# 2nd_version.net
KiCad netlist of a schematic drawn in EAGLE
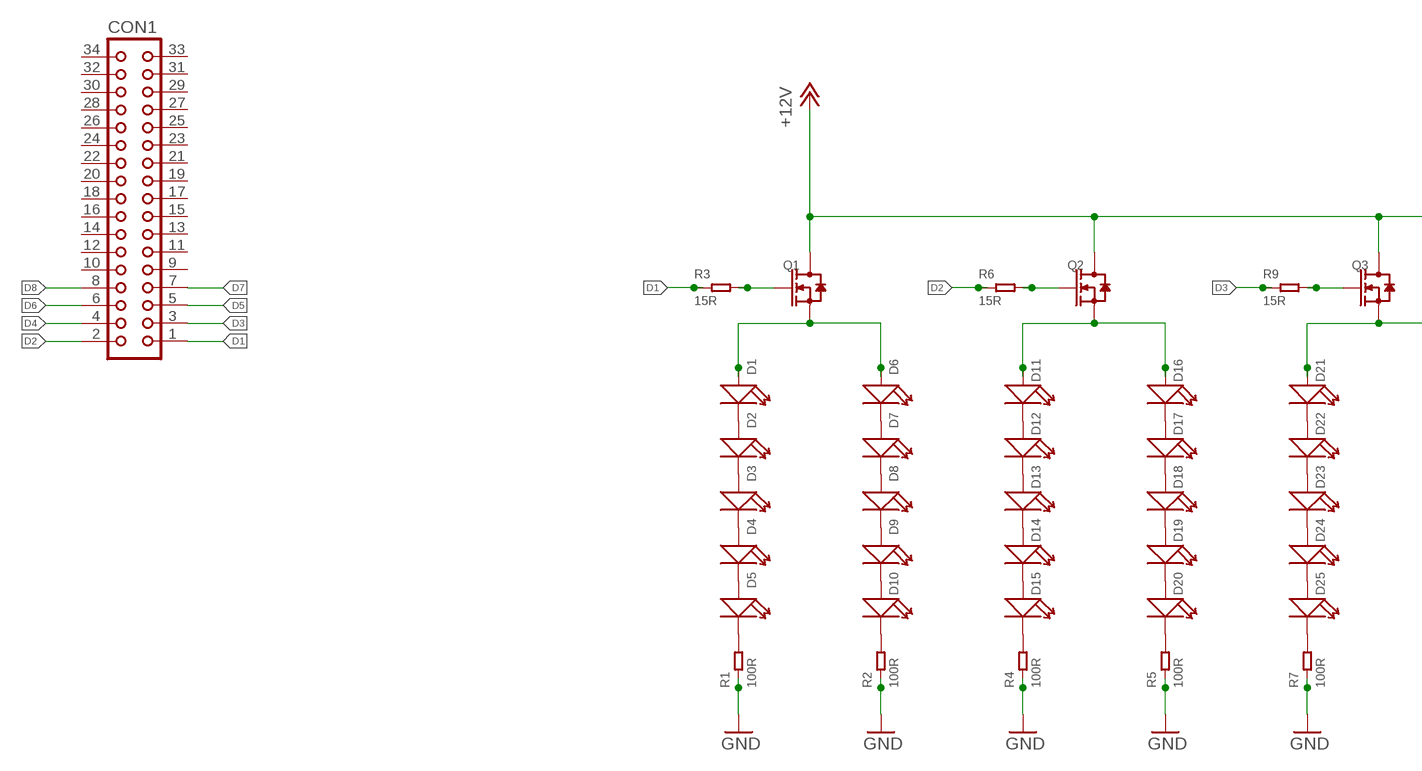
[diagram p0: schematic, sheet 1, part 1 of 2]
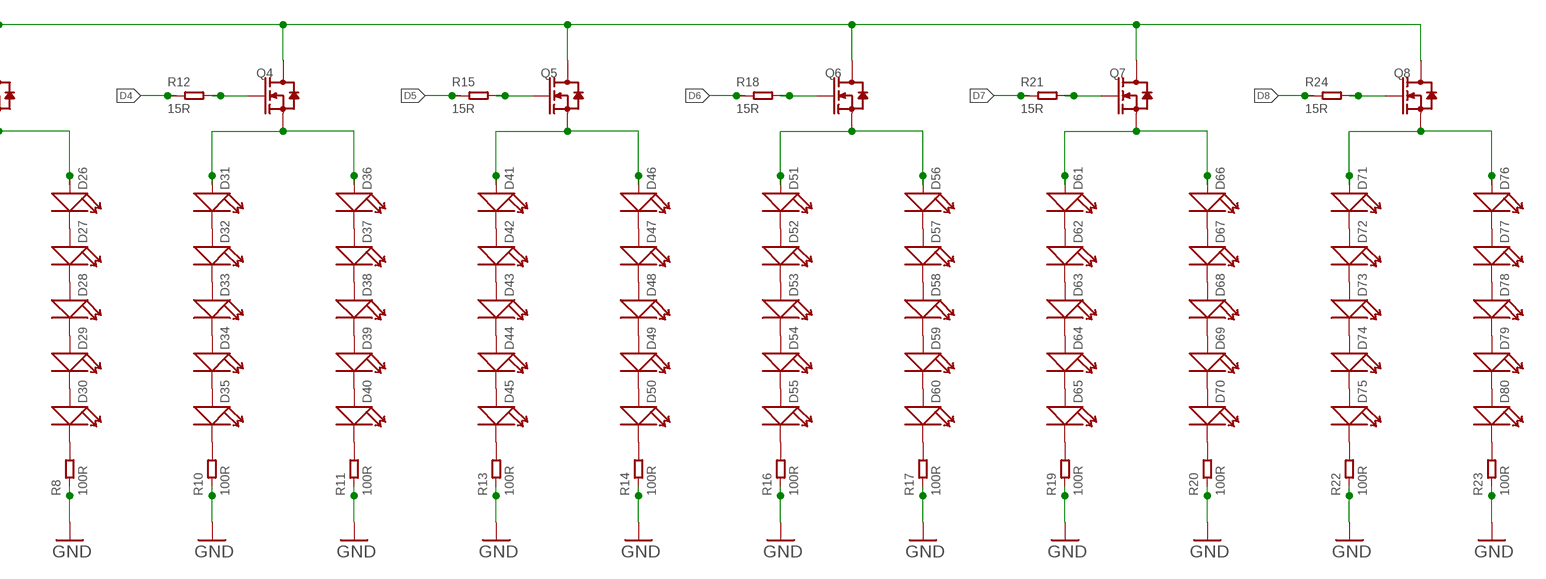
[diagram p1: schematic, sheet 1, part 2 of 2]

(export (version "E")
  (design (tool "Eeschema 10.0.6"))
  (components
    (comp (ref "CON1")
      (value "CON34L")
      (footprint "eagle-import:CON34L")
      (libsource (lib "eagle-import") (part "CON34L"))
    )
    (comp (ref "D1")
      (value "SMD-LED-CLEAR-YELLOW(0603)")
      (footprint "eagle-import:LED-0603")
      (fields (field (name "MPN") "19-217-Y5C-AM1N1VY-3T"))
      (libsource (lib "eagle-import") (part "SMD-LED-CLEAR-YELLOW(0603)"))
    )
    (comp (ref "D2")
      (value "SMD-LED-CLEAR-YELLOW(0603)")
      (footprint "eagle-import:LED-0603")
      (fields (field (name "MPN") "19-217-Y5C-AM1N1VY-3T"))
      (libsource (lib "eagle-import") (part "SMD-LED-CLEAR-YELLOW(0603)"))
    )
    (comp (ref "D3")
      (value "SMD-LED-CLEAR-YELLOW(0603)")
      (footprint "eagle-import:LED-0603")
      (fields (field (name "MPN") "19-217-Y5C-AM1N1VY-3T"))
      (libsource (lib "eagle-import") (part "SMD-LED-CLEAR-YELLOW(0603)"))
    )
    (comp (ref "D4")
      (value "SMD-LED-CLEAR-YELLOW(0603)")
      (footprint "eagle-import:LED-0603")
      (fields (field (name "MPN") "19-217-Y5C-AM1N1VY-3T"))
      (libsource (lib "eagle-import") (part "SMD-LED-CLEAR-YELLOW(0603)"))
    )
    (comp (ref "D5")
      (value "SMD-LED-CLEAR-YELLOW(0603)")
      (footprint "eagle-import:LED-0603")
      (fields (field (name "MPN") "19-217-Y5C-AM1N1VY-3T"))
      (libsource (lib "eagle-import") (part "SMD-LED-CLEAR-YELLOW(0603)"))
    )
    (comp (ref "D6")
      (value "SMD-LED-CLEAR-YELLOW(0603)")
      (footprint "eagle-import:LED-0603")
      (fields (field (name "MPN") "19-217-Y5C-AM1N1VY-3T"))
      (libsource (lib "eagle-import") (part "SMD-LED-CLEAR-YELLOW(0603)"))
    )
    (comp (ref "D7")
      (value "SMD-LED-CLEAR-YELLOW(0603)")
      (footprint "eagle-import:LED-0603")
      (fields (field (name "MPN") "19-217-Y5C-AM1N1VY-3T"))
      (libsource (lib "eagle-import") (part "SMD-LED-CLEAR-YELLOW(0603)"))
    )
    (comp (ref "D8")
      (value "SMD-LED-CLEAR-YELLOW(0603)")
      (footprint "eagle-import:LED-0603")
      (fields (field (name "MPN") "19-217-Y5C-AM1N1VY-3T"))
      (libsource (lib "eagle-import") (part "SMD-LED-CLEAR-YELLOW(0603)"))
    )
    (comp (ref "D9")
      (value "SMD-LED-CLEAR-YELLOW(0603)")
      (footprint "eagle-import:LED-0603")
      (fields (field (name "MPN") "19-217-Y5C-AM1N1VY-3T"))
      (libsource (lib "eagle-import") (part "SMD-LED-CLEAR-YELLOW(0603)"))
    )
    (comp (ref "D10")
      (value "SMD-LED-CLEAR-YELLOW(0603)")
      (footprint "eagle-import:LED-0603")
      (fields (field (name "MPN") "19-217-Y5C-AM1N1VY-3T"))
      (libsource (lib "eagle-import") (part "SMD-LED-CLEAR-YELLOW(0603)"))
    )
    (comp (ref "D11")
      (value "SMD-LED-CLEAR-YELLOW(0603)")
      (footprint "eagle-import:LED-0603")
      (fields (field (name "MPN") "19-217-Y5C-AM1N1VY-3T"))
      (libsource (lib "eagle-import") (part "SMD-LED-CLEAR-YELLOW(0603)"))
    )
    (comp (ref "D12")
      (value "SMD-LED-CLEAR-YELLOW(0603)")
      (footprint "eagle-import:LED-0603")
      (fields (field (name "MPN") "19-217-Y5C-AM1N1VY-3T"))
      (libsource (lib "eagle-import") (part "SMD-LED-CLEAR-YELLOW(0603)"))
    )
    (comp (ref "D13")
      (value "SMD-LED-CLEAR-YELLOW(0603)")
      (footprint "eagle-import:LED-0603")
      (fields (field (name "MPN") "19-217-Y5C-AM1N1VY-3T"))
      (libsource (lib "eagle-import") (part "SMD-LED-CLEAR-YELLOW(0603)"))
    )
    (comp (ref "D14")
      (value "SMD-LED-CLEAR-YELLOW(0603)")
      (footprint "eagle-import:LED-0603")
      (fields (field (name "MPN") "19-217-Y5C-AM1N1VY-3T"))
      (libsource (lib "eagle-import") (part "SMD-LED-CLEAR-YELLOW(0603)"))
    )
    (comp (ref "D15")
      (value "SMD-LED-CLEAR-YELLOW(0603)")
      (footprint "eagle-import:LED-0603")
      (fields (field (name "MPN") "19-217-Y5C-AM1N1VY-3T"))
      (libsource (lib "eagle-import") (part "SMD-LED-CLEAR-YELLOW(0603)"))
    )
    (comp (ref "D16")
      (value "SMD-LED-CLEAR-YELLOW(0603)")
      (footprint "eagle-import:LED-0603")
      (fields (field (name "MPN") "19-217-Y5C-AM1N1VY-3T"))
      (libsource (lib "eagle-import") (part "SMD-LED-CLEAR-YELLOW(0603)"))
    )
    (comp (ref "D17")
      (value "SMD-LED-CLEAR-YELLOW(0603)")
      (footprint "eagle-import:LED-0603")
      (fields (field (name "MPN") "19-217-Y5C-AM1N1VY-3T"))
      (libsource (lib "eagle-import") (part "SMD-LED-CLEAR-YELLOW(0603)"))
    )
    (comp (ref "D18")
      (value "SMD-LED-CLEAR-YELLOW(0603)")
      (footprint "eagle-import:LED-0603")
      (fields (field (name "MPN") "19-217-Y5C-AM1N1VY-3T"))
      (libsource (lib "eagle-import") (part "SMD-LED-CLEAR-YELLOW(0603)"))
    )
    (comp (ref "D19")
      (value "SMD-LED-CLEAR-YELLOW(0603)")
      (footprint "eagle-import:LED-0603")
      (fields (field (name "MPN") "19-217-Y5C-AM1N1VY-3T"))
      (libsource (lib "eagle-import") (part "SMD-LED-CLEAR-YELLOW(0603)"))
    )
    (comp (ref "D20")
      (value "SMD-LED-CLEAR-YELLOW(0603)")
      (footprint "eagle-import:LED-0603")
      (fields (field (name "MPN") "19-217-Y5C-AM1N1VY-3T"))
      (libsource (lib "eagle-import") (part "SMD-LED-CLEAR-YELLOW(0603)"))
    )
    (comp (ref "D21")
      (value "SMD-LED-CLEAR-YELLOW(0603)")
      (footprint "eagle-import:LED-0603")
      (fields (field (name "MPN") "19-217-Y5C-AM1N1VY-3T"))
      (libsource (lib "eagle-import") (part "SMD-LED-CLEAR-YELLOW(0603)"))
    )
    (comp (ref "D22")
      (value "SMD-LED-CLEAR-YELLOW(0603)")
      (footprint "eagle-import:LED-0603")
      (fields (field (name "MPN") "19-217-Y5C-AM1N1VY-3T"))
      (libsource (lib "eagle-import") (part "SMD-LED-CLEAR-YELLOW(0603)"))
    )
    (comp (ref "D23")
      (value "SMD-LED-CLEAR-YELLOW(0603)")
      (footprint "eagle-import:LED-0603")
      (fields (field (name "MPN") "19-217-Y5C-AM1N1VY-3T"))
      (libsource (lib "eagle-import") (part "SMD-LED-CLEAR-YELLOW(0603)"))
    )
    (comp (ref "D24")
      (value "SMD-LED-CLEAR-YELLOW(0603)")
      (footprint "eagle-import:LED-0603")
      (fields (field (name "MPN") "19-217-Y5C-AM1N1VY-3T"))
      (libsource (lib "eagle-import") (part "SMD-LED-CLEAR-YELLOW(0603)"))
    )
    (comp (ref "D25")
      (value "SMD-LED-CLEAR-YELLOW(0603)")
      (footprint "eagle-import:LED-0603")
      (fields (field (name "MPN") "19-217-Y5C-AM1N1VY-3T"))
      (libsource (lib "eagle-import") (part "SMD-LED-CLEAR-YELLOW(0603)"))
    )
    (comp (ref "D26")
      (value "SMD-LED-CLEAR-YELLOW(0603)")
      (footprint "eagle-import:LED-0603")
      (fields (field (name "MPN") "19-217-Y5C-AM1N1VY-3T"))
      (libsource (lib "eagle-import") (part "SMD-LED-CLEAR-YELLOW(0603)"))
    )
    (comp (ref "D27")
      (value "SMD-LED-CLEAR-YELLOW(0603)")
      (footprint "eagle-import:LED-0603")
      (fields (field (name "MPN") "19-217-Y5C-AM1N1VY-3T"))
      (libsource (lib "eagle-import") (part "SMD-LED-CLEAR-YELLOW(0603)"))
    )
    (comp (ref "D28")
      (value "SMD-LED-CLEAR-YELLOW(0603)")
      (footprint "eagle-import:LED-0603")
      (fields (field (name "MPN") "19-217-Y5C-AM1N1VY-3T"))
      (libsource (lib "eagle-import") (part "SMD-LED-CLEAR-YELLOW(0603)"))
    )
    (comp (ref "D29")
      (value "SMD-LED-CLEAR-YELLOW(0603)")
      (footprint "eagle-import:LED-0603")
      (fields (field (name "MPN") "19-217-Y5C-AM1N1VY-3T"))
      (libsource (lib "eagle-import") (part "SMD-LED-CLEAR-YELLOW(0603)"))
    )
    (comp (ref "D30")
      (value "SMD-LED-CLEAR-YELLOW(0603)")
      (footprint "eagle-import:LED-0603")
      (fields (field (name "MPN") "19-217-Y5C-AM1N1VY-3T"))
      (libsource (lib "eagle-import") (part "SMD-LED-CLEAR-YELLOW(0603)"))
    )
    (comp (ref "D31")
      (value "SMD-LED-CLEAR-YELLOW(0603)")
      (footprint "eagle-import:LED-0603")
      (fields (field (name "MPN") "19-217-Y5C-AM1N1VY-3T"))
      (libsource (lib "eagle-import") (part "SMD-LED-CLEAR-YELLOW(0603)"))
    )
    (comp (ref "D32")
      (value "SMD-LED-CLEAR-YELLOW(0603)")
      (footprint "eagle-import:LED-0603")
      (fields (field (name "MPN") "19-217-Y5C-AM1N1VY-3T"))
      (libsource (lib "eagle-import") (part "SMD-LED-CLEAR-YELLOW(0603)"))
    )
    (comp (ref "D33")
      (value "SMD-LED-CLEAR-YELLOW(0603)")
      (footprint "eagle-import:LED-0603")
      (fields (field (name "MPN") "19-217-Y5C-AM1N1VY-3T"))
      (libsource (lib "eagle-import") (part "SMD-LED-CLEAR-YELLOW(0603)"))
    )
    (comp (ref "D34")
      (value "SMD-LED-CLEAR-YELLOW(0603)")
      (footprint "eagle-import:LED-0603")
      (fields (field (name "MPN") "19-217-Y5C-AM1N1VY-3T"))
      (libsource (lib "eagle-import") (part "SMD-LED-CLEAR-YELLOW(0603)"))
    )
    (comp (ref "D35")
      (value "SMD-LED-CLEAR-YELLOW(0603)")
      (footprint "eagle-import:LED-0603")
      (fields (field (name "MPN") "19-217-Y5C-AM1N1VY-3T"))
      (libsource (lib "eagle-import") (part "SMD-LED-CLEAR-YELLOW(0603)"))
    )
    (comp (ref "D36")
      (value "SMD-LED-CLEAR-YELLOW(0603)")
      (footprint "eagle-import:LED-0603")
      (fields (field (name "MPN") "19-217-Y5C-AM1N1VY-3T"))
      (libsource (lib "eagle-import") (part "SMD-LED-CLEAR-YELLOW(0603)"))
    )
    (comp (ref "D37")
      (value "SMD-LED-CLEAR-YELLOW(0603)")
      (footprint "eagle-import:LED-0603")
      (fields (field (name "MPN") "19-217-Y5C-AM1N1VY-3T"))
      (libsource (lib "eagle-import") (part "SMD-LED-CLEAR-YELLOW(0603)"))
    )
    (comp (ref "D38")
      (value "SMD-LED-CLEAR-YELLOW(0603)")
      (footprint "eagle-import:LED-0603")
      (fields (field (name "MPN") "19-217-Y5C-AM1N1VY-3T"))
      (libsource (lib "eagle-import") (part "SMD-LED-CLEAR-YELLOW(0603)"))
    )
    (comp (ref "D39")
      (value "SMD-LED-CLEAR-YELLOW(0603)")
      (footprint "eagle-import:LED-0603")
      (fields (field (name "MPN") "19-217-Y5C-AM1N1VY-3T"))
      (libsource (lib "eagle-import") (part "SMD-LED-CLEAR-YELLOW(0603)"))
    )
    (comp (ref "D40")
      (value "SMD-LED-CLEAR-YELLOW(0603)")
      (footprint "eagle-import:LED-0603")
      (fields (field (name "MPN") "19-217-Y5C-AM1N1VY-3T"))
      (libsource (lib "eagle-import") (part "SMD-LED-CLEAR-YELLOW(0603)"))
    )
    (comp (ref "D41")
      (value "SMD-LED-CLEAR-YELLOW(0603)")
      (footprint "eagle-import:LED-0603")
      (fields (field (name "MPN") "19-217-Y5C-AM1N1VY-3T"))
      (libsource (lib "eagle-import") (part "SMD-LED-CLEAR-YELLOW(0603)"))
    )
    (comp (ref "D42")
      (value "SMD-LED-CLEAR-YELLOW(0603)")
      (footprint "eagle-import:LED-0603")
      (fields (field (name "MPN") "19-217-Y5C-AM1N1VY-3T"))
      (libsource (lib "eagle-import") (part "SMD-LED-CLEAR-YELLOW(0603)"))
    )
    (comp (ref "D43")
      (value "SMD-LED-CLEAR-YELLOW(0603)")
      (footprint "eagle-import:LED-0603")
      (fields (field (name "MPN") "19-217-Y5C-AM1N1VY-3T"))
      (libsource (lib "eagle-import") (part "SMD-LED-CLEAR-YELLOW(0603)"))
    )
    (comp (ref "D44")
      (value "SMD-LED-CLEAR-YELLOW(0603)")
      (footprint "eagle-import:LED-0603")
      (fields (field (name "MPN") "19-217-Y5C-AM1N1VY-3T"))
      (libsource (lib "eagle-import") (part "SMD-LED-CLEAR-YELLOW(0603)"))
    )
    (comp (ref "D45")
      (value "SMD-LED-CLEAR-YELLOW(0603)")
      (footprint "eagle-import:LED-0603")
      (fields (field (name "MPN") "19-217-Y5C-AM1N1VY-3T"))
      (libsource (lib "eagle-import") (part "SMD-LED-CLEAR-YELLOW(0603)"))
    )
    (comp (ref "D46")
      (value "SMD-LED-CLEAR-YELLOW(0603)")
      (footprint "eagle-import:LED-0603")
      (fields (field (name "MPN") "19-217-Y5C-AM1N1VY-3T"))
      (libsource (lib "eagle-import") (part "SMD-LED-CLEAR-YELLOW(0603)"))
    )
    (comp (ref "D47")
      (value "SMD-LED-CLEAR-YELLOW(0603)")
      (footprint "eagle-import:LED-0603")
      (fields (field (name "MPN") "19-217-Y5C-AM1N1VY-3T"))
      (libsource (lib "eagle-import") (part "SMD-LED-CLEAR-YELLOW(0603)"))
    )
    (comp (ref "D48")
      (value "SMD-LED-CLEAR-YELLOW(0603)")
      (footprint "eagle-import:LED-0603")
      (fields (field (name "MPN") "19-217-Y5C-AM1N1VY-3T"))
      (libsource (lib "eagle-import") (part "SMD-LED-CLEAR-YELLOW(0603)"))
    )
    (comp (ref "D49")
      (value "SMD-LED-CLEAR-YELLOW(0603)")
      (footprint "eagle-import:LED-0603")
      (fields (field (name "MPN") "19-217-Y5C-AM1N1VY-3T"))
      (libsource (lib "eagle-import") (part "SMD-LED-CLEAR-YELLOW(0603)"))
    )
    (comp (ref "D50")
      (value "SMD-LED-CLEAR-YELLOW(0603)")
      (footprint "eagle-import:LED-0603")
      (fields (field (name "MPN") "19-217-Y5C-AM1N1VY-3T"))
      (libsource (lib "eagle-import") (part "SMD-LED-CLEAR-YELLOW(0603)"))
    )
    (comp (ref "D51")
      (value "SMD-LED-CLEAR-YELLOW(0603)")
      (footprint "eagle-import:LED-0603")
      (fields (field (name "MPN") "19-217-Y5C-AM1N1VY-3T"))
      (libsource (lib "eagle-import") (part "SMD-LED-CLEAR-YELLOW(0603)"))
    )
    (comp (ref "D52")
      (value "SMD-LED-CLEAR-YELLOW(0603)")
      (footprint "eagle-import:LED-0603")
      (fields (field (name "MPN") "19-217-Y5C-AM1N1VY-3T"))
      (libsource (lib "eagle-import") (part "SMD-LED-CLEAR-YELLOW(0603)"))
    )
    (comp (ref "D53")
      (value "SMD-LED-CLEAR-YELLOW(0603)")
      (footprint "eagle-import:LED-0603")
      (fields (field (name "MPN") "19-217-Y5C-AM1N1VY-3T"))
      (libsource (lib "eagle-import") (part "SMD-LED-CLEAR-YELLOW(0603)"))
    )
    (comp (ref "D54")
      (value "SMD-LED-CLEAR-YELLOW(0603)")
      (footprint "eagle-import:LED-0603")
      (fields (field (name "MPN") "19-217-Y5C-AM1N1VY-3T"))
      (libsource (lib "eagle-import") (part "SMD-LED-CLEAR-YELLOW(0603)"))
    )
    (comp (ref "D55")
      (value "SMD-LED-CLEAR-YELLOW(0603)")
      (footprint "eagle-import:LED-0603")
      (fields (field (name "MPN") "19-217-Y5C-AM1N1VY-3T"))
      (libsource (lib "eagle-import") (part "SMD-LED-CLEAR-YELLOW(0603)"))
    )
    (comp (ref "D56")
      (value "SMD-LED-CLEAR-YELLOW(0603)")
      (footprint "eagle-import:LED-0603")
      (fields (field (name "MPN") "19-217-Y5C-AM1N1VY-3T"))
      (libsource (lib "eagle-import") (part "SMD-LED-CLEAR-YELLOW(0603)"))
    )
    (comp (ref "D57")
      (value "SMD-LED-CLEAR-YELLOW(0603)")
      (footprint "eagle-import:LED-0603")
      (fields (field (name "MPN") "19-217-Y5C-AM1N1VY-3T"))
      (libsource (lib "eagle-import") (part "SMD-LED-CLEAR-YELLOW(0603)"))
    )
    (comp (ref "D58")
      (value "SMD-LED-CLEAR-YELLOW(0603)")
      (footprint "eagle-import:LED-0603")
      (fields (field (name "MPN") "19-217-Y5C-AM1N1VY-3T"))
      (libsource (lib "eagle-import") (part "SMD-LED-CLEAR-YELLOW(0603)"))
    )
    (comp (ref "D59")
      (value "SMD-LED-CLEAR-YELLOW(0603)")
      (footprint "eagle-import:LED-0603")
      (fields (field (name "MPN") "19-217-Y5C-AM1N1VY-3T"))
      (libsource (lib "eagle-import") (part "SMD-LED-CLEAR-YELLOW(0603)"))
    )
    (comp (ref "D60")
      (value "SMD-LED-CLEAR-YELLOW(0603)")
      (footprint "eagle-import:LED-0603")
      (fields (field (name "MPN") "19-217-Y5C-AM1N1VY-3T"))
      (libsource (lib "eagle-import") (part "SMD-LED-CLEAR-YELLOW(0603)"))
    )
    (comp (ref "D61")
      (value "SMD-LED-CLEAR-YELLOW(0603)")
      (footprint "eagle-import:LED-0603")
      (fields (field (name "MPN") "19-217-Y5C-AM1N1VY-3T"))
      (libsource (lib "eagle-import") (part "SMD-LED-CLEAR-YELLOW(0603)"))
    )
    (comp (ref "D62")
      (value "SMD-LED-CLEAR-YELLOW(0603)")
      (footprint "eagle-import:LED-0603")
      (fields (field (name "MPN") "19-217-Y5C-AM1N1VY-3T"))
      (libsource (lib "eagle-import") (part "SMD-LED-CLEAR-YELLOW(0603)"))
    )
    (comp (ref "D63")
      (value "SMD-LED-CLEAR-YELLOW(0603)")
      (footprint "eagle-import:LED-0603")
      (fields (field (name "MPN") "19-217-Y5C-AM1N1VY-3T"))
      (libsource (lib "eagle-import") (part "SMD-LED-CLEAR-YELLOW(0603)"))
    )
    (comp (ref "D64")
      (value "SMD-LED-CLEAR-YELLOW(0603)")
      (footprint "eagle-import:LED-0603")
      (fields (field (name "MPN") "19-217-Y5C-AM1N1VY-3T"))
      (libsource (lib "eagle-import") (part "SMD-LED-CLEAR-YELLOW(0603)"))
    )
    (comp (ref "D65")
      (value "SMD-LED-CLEAR-YELLOW(0603)")
      (footprint "eagle-import:LED-0603")
      (fields (field (name "MPN") "19-217-Y5C-AM1N1VY-3T"))
      (libsource (lib "eagle-import") (part "SMD-LED-CLEAR-YELLOW(0603)"))
    )
    (comp (ref "D66")
      (value "SMD-LED-CLEAR-YELLOW(0603)")
      (footprint "eagle-import:LED-0603")
      (fields (field (name "MPN") "19-217-Y5C-AM1N1VY-3T"))
      (libsource (lib "eagle-import") (part "SMD-LED-CLEAR-YELLOW(0603)"))
    )
    (comp (ref "D67")
      (value "SMD-LED-CLEAR-YELLOW(0603)")
      (footprint "eagle-import:LED-0603")
      (fields (field (name "MPN") "19-217-Y5C-AM1N1VY-3T"))
      (libsource (lib "eagle-import") (part "SMD-LED-CLEAR-YELLOW(0603)"))
    )
    (comp (ref "D68")
      (value "SMD-LED-CLEAR-YELLOW(0603)")
      (footprint "eagle-import:LED-0603")
      (fields (field (name "MPN") "19-217-Y5C-AM1N1VY-3T"))
      (libsource (lib "eagle-import") (part "SMD-LED-CLEAR-YELLOW(0603)"))
    )
    (comp (ref "D69")
      (value "SMD-LED-CLEAR-YELLOW(0603)")
      (footprint "eagle-import:LED-0603")
      (fields (field (name "MPN") "19-217-Y5C-AM1N1VY-3T"))
      (libsource (lib "eagle-import") (part "SMD-LED-CLEAR-YELLOW(0603)"))
    )
    (comp (ref "D70")
      (value "SMD-LED-CLEAR-YELLOW(0603)")
      (footprint "eagle-import:LED-0603")
      (fields (field (name "MPN") "19-217-Y5C-AM1N1VY-3T"))
      (libsource (lib "eagle-import") (part "SMD-LED-CLEAR-YELLOW(0603)"))
    )
    (comp (ref "D71")
      (value "SMD-LED-CLEAR-YELLOW(0603)")
      (footprint "eagle-import:LED-0603")
      (fields (field (name "MPN") "19-217-Y5C-AM1N1VY-3T"))
      (libsource (lib "eagle-import") (part "SMD-LED-CLEAR-YELLOW(0603)"))
    )
    (comp (ref "D72")
      (value "SMD-LED-CLEAR-YELLOW(0603)")
      (footprint "eagle-import:LED-0603")
      (fields (field (name "MPN") "19-217-Y5C-AM1N1VY-3T"))
      (libsource (lib "eagle-import") (part "SMD-LED-CLEAR-YELLOW(0603)"))
    )
    (comp (ref "D73")
      (value "SMD-LED-CLEAR-YELLOW(0603)")
      (footprint "eagle-import:LED-0603")
      (fields (field (name "MPN") "19-217-Y5C-AM1N1VY-3T"))
      (libsource (lib "eagle-import") (part "SMD-LED-CLEAR-YELLOW(0603)"))
    )
    (comp (ref "D74")
      (value "SMD-LED-CLEAR-YELLOW(0603)")
      (footprint "eagle-import:LED-0603")
      (fields (field (name "MPN") "19-217-Y5C-AM1N1VY-3T"))
      (libsource (lib "eagle-import") (part "SMD-LED-CLEAR-YELLOW(0603)"))
    )
    (comp (ref "D75")
      (value "SMD-LED-CLEAR-YELLOW(0603)")
      (footprint "eagle-import:LED-0603")
      (fields (field (name "MPN") "19-217-Y5C-AM1N1VY-3T"))
      (libsource (lib "eagle-import") (part "SMD-LED-CLEAR-YELLOW(0603)"))
    )
    (comp (ref "D76")
      (value "SMD-LED-CLEAR-YELLOW(0603)")
      (footprint "eagle-import:LED-0603")
      (fields (field (name "MPN") "19-217-Y5C-AM1N1VY-3T"))
      (libsource (lib "eagle-import") (part "SMD-LED-CLEAR-YELLOW(0603)"))
    )
    (comp (ref "D77")
      (value "SMD-LED-CLEAR-YELLOW(0603)")
      (footprint "eagle-import:LED-0603")
      (fields (field (name "MPN") "19-217-Y5C-AM1N1VY-3T"))
      (libsource (lib "eagle-import") (part "SMD-LED-CLEAR-YELLOW(0603)"))
    )
    (comp (ref "D78")
      (value "SMD-LED-CLEAR-YELLOW(0603)")
      (footprint "eagle-import:LED-0603")
      (fields (field (name "MPN") "19-217-Y5C-AM1N1VY-3T"))
      (libsource (lib "eagle-import") (part "SMD-LED-CLEAR-YELLOW(0603)"))
    )
    (comp (ref "D79")
      (value "SMD-LED-CLEAR-YELLOW(0603)")
      (footprint "eagle-import:LED-0603")
      (fields (field (name "MPN") "19-217-Y5C-AM1N1VY-3T"))
      (libsource (lib "eagle-import") (part "SMD-LED-CLEAR-YELLOW(0603)"))
    )
    (comp (ref "D80")
      (value "SMD-LED-CLEAR-YELLOW(0603)")
      (footprint "eagle-import:LED-0603")
      (fields (field (name "MPN") "19-217-Y5C-AM1N1VY-3T"))
      (libsource (lib "eagle-import") (part "SMD-LED-CLEAR-YELLOW(0603)"))
    )
    (comp (ref "Q1")
      (value "SMD-MOSFET-N-CH-20V-2.1A(SOT-23)")
      (footprint "eagle-import:SOT-23")
      (fields (field (name "MPN") "CJ2302"))
      (libsource (lib "eagle-import") (part "SMD-MOSFET-N-CH-20V-2.1A(SOT-23)"))
    )
    (comp (ref "Q2")
      (value "SMD-MOSFET-N-CH-20V-2.1A(SOT-23)")
      (footprint "eagle-import:SOT-23")
      (fields (field (name "MPN") "CJ2302"))
      (libsource (lib "eagle-import") (part "SMD-MOSFET-N-CH-20V-2.1A(SOT-23)"))
    )
    (comp (ref "Q3")
      (value "SMD-MOSFET-N-CH-20V-2.1A(SOT-23)")
      (footprint "eagle-import:SOT-23")
      (fields (field (name "MPN") "CJ2302"))
      (libsource (lib "eagle-import") (part "SMD-MOSFET-N-CH-20V-2.1A(SOT-23)"))
    )
    (comp (ref "Q4")
      (value "SMD-MOSFET-N-CH-20V-2.1A(SOT-23)")
      (footprint "eagle-import:SOT-23")
      (fields (field (name "MPN") "CJ2302"))
      (libsource (lib "eagle-import") (part "SMD-MOSFET-N-CH-20V-2.1A(SOT-23)"))
    )
    (comp (ref "Q5")
      (value "SMD-MOSFET-N-CH-20V-2.1A(SOT-23)")
      (footprint "eagle-import:SOT-23")
      (fields (field (name "MPN") "CJ2302"))
      (libsource (lib "eagle-import") (part "SMD-MOSFET-N-CH-20V-2.1A(SOT-23)"))
    )
    (comp (ref "Q6")
      (value "SMD-MOSFET-N-CH-20V-2.1A(SOT-23)")
      (footprint "eagle-import:SOT-23")
      (fields (field (name "MPN") "CJ2302"))
      (libsource (lib "eagle-import") (part "SMD-MOSFET-N-CH-20V-2.1A(SOT-23)"))
    )
    (comp (ref "Q7")
      (value "SMD-MOSFET-N-CH-20V-2.1A(SOT-23)")
      (footprint "eagle-import:SOT-23")
      (fields (field (name "MPN") "CJ2302"))
      (libsource (lib "eagle-import") (part "SMD-MOSFET-N-CH-20V-2.1A(SOT-23)"))
    )
    (comp (ref "Q8")
      (value "SMD-MOSFET-N-CH-20V-2.1A(SOT-23)")
      (footprint "eagle-import:SOT-23")
      (fields (field (name "MPN") "CJ2302"))
      (libsource (lib "eagle-import") (part "SMD-MOSFET-N-CH-20V-2.1A(SOT-23)"))
    )
    (comp (ref "R1")
      (value "100R")
      (footprint "eagle-import:R0805")
      (fields (field (name "MPN") "RC0805JR-07100RL"))
      (libsource (lib "eagle-import") (part "SMD-RES-100R-5%-1/8W(0805)"))
    )
    (comp (ref "R2")
      (value "100R")
      (footprint "eagle-import:R0805")
      (fields (field (name "MPN") "RC0805JR-07100RL"))
      (libsource (lib "eagle-import") (part "SMD-RES-100R-5%-1/8W(0805)"))
    )
    (comp (ref "R3")
      (value "15R")
      (footprint "eagle-import:R0603")
      (fields (field (name "MPN") "RC0603JR-0715RL"))
      (libsource (lib "eagle-import") (part "SMD-RES-15R-5%-1/10W(0603)"))
    )
    (comp (ref "R4")
      (value "100R")
      (footprint "eagle-import:R0805")
      (fields (field (name "MPN") "RC0805JR-07100RL"))
      (libsource (lib "eagle-import") (part "SMD-RES-100R-5%-1/8W(0805)"))
    )
    (comp (ref "R5")
      (value "100R")
      (footprint "eagle-import:R0805")
      (fields (field (name "MPN") "RC0805JR-07100RL"))
      (libsource (lib "eagle-import") (part "SMD-RES-100R-5%-1/8W(0805)"))
    )
    (comp (ref "R6")
      (value "15R")
      (footprint "eagle-import:R0603")
      (fields (field (name "MPN") "RC0603JR-0715RL"))
      (libsource (lib "eagle-import") (part "SMD-RES-15R-5%-1/10W(0603)"))
    )
    (comp (ref "R7")
      (value "100R")
      (footprint "eagle-import:R0805")
      (fields (field (name "MPN") "RC0805JR-07100RL"))
      (libsource (lib "eagle-import") (part "SMD-RES-100R-5%-1/8W(0805)"))
    )
    (comp (ref "R8")
      (value "100R")
      (footprint "eagle-import:R0805")
      (fields (field (name "MPN") "RC0805JR-07100RL"))
      (libsource (lib "eagle-import") (part "SMD-RES-100R-5%-1/8W(0805)"))
    )
    (comp (ref "R9")
      (value "15R")
      (footprint "eagle-import:R0603")
      (fields (field (name "MPN") "RC0603JR-0715RL"))
      (libsource (lib "eagle-import") (part "SMD-RES-15R-5%-1/10W(0603)"))
    )
    (comp (ref "R10")
      (value "100R")
      (footprint "eagle-import:R0805")
      (fields (field (name "MPN") "RC0805JR-07100RL"))
      (libsource (lib "eagle-import") (part "SMD-RES-100R-5%-1/8W(0805)"))
    )
    (comp (ref "R11")
      (value "100R")
      (footprint "eagle-import:R0805")
      (fields (field (name "MPN") "RC0805JR-07100RL"))
      (libsource (lib "eagle-import") (part "SMD-RES-100R-5%-1/8W(0805)"))
    )
    (comp (ref "R12")
      (value "15R")
      (footprint "eagle-import:R0603")
      (fields (field (name "MPN") "RC0603JR-0715RL"))
      (libsource (lib "eagle-import") (part "SMD-RES-15R-5%-1/10W(0603)"))
    )
    (comp (ref "R13")
      (value "100R")
      (footprint "eagle-import:R0805")
      (fields (field (name "MPN") "RC0805JR-07100RL"))
      (libsource (lib "eagle-import") (part "SMD-RES-100R-5%-1/8W(0805)"))
    )
    (comp (ref "R14")
      (value "100R")
      (footprint "eagle-import:R0805")
      (fields (field (name "MPN") "RC0805JR-07100RL"))
      (libsource (lib "eagle-import") (part "SMD-RES-100R-5%-1/8W(0805)"))
    )
    (comp (ref "R15")
      (value "15R")
      (footprint "eagle-import:R0603")
      (fields (field (name "MPN") "RC0603JR-0715RL"))
      (libsource (lib "eagle-import") (part "SMD-RES-15R-5%-1/10W(0603)"))
    )
    (comp (ref "R16")
      (value "100R")
      (footprint "eagle-import:R0805")
      (fields (field (name "MPN") "RC0805JR-07100RL"))
      (libsource (lib "eagle-import") (part "SMD-RES-100R-5%-1/8W(0805)"))
    )
    (comp (ref "R17")
      (value "100R")
      (footprint "eagle-import:R0805")
      (fields (field (name "MPN") "RC0805JR-07100RL"))
      (libsource (lib "eagle-import") (part "SMD-RES-100R-5%-1/8W(0805)"))
    )
    (comp (ref "R18")
      (value "15R")
      (footprint "eagle-import:R0603")
      (fields (field (name "MPN") "RC0603JR-0715RL"))
      (libsource (lib "eagle-import") (part "SMD-RES-15R-5%-1/10W(0603)"))
    )
    (comp (ref "R19")
      (value "100R")
      (footprint "eagle-import:R0805")
      (fields (field (name "MPN") "RC0805JR-07100RL"))
      (libsource (lib "eagle-import") (part "SMD-RES-100R-5%-1/8W(0805)"))
    )
    (comp (ref "R20")
      (value "100R")
      (footprint "eagle-import:R0805")
      (fields (field (name "MPN") "RC0805JR-07100RL"))
      (libsource (lib "eagle-import") (part "SMD-RES-100R-5%-1/8W(0805)"))
    )
    (comp (ref "R21")
      (value "15R")
      (footprint "eagle-import:R0603")
      (fields (field (name "MPN") "RC0603JR-0715RL"))
      (libsource (lib "eagle-import") (part "SMD-RES-15R-5%-1/10W(0603)"))
    )
    (comp (ref "R22")
      (value "100R")
      (footprint "eagle-import:R0805")
      (fields (field (name "MPN") "RC0805JR-07100RL"))
      (libsource (lib "eagle-import") (part "SMD-RES-100R-5%-1/8W(0805)"))
    )
    (comp (ref "R23")
      (value "100R")
      (footprint "eagle-import:R0805")
      (fields (field (name "MPN") "RC0805JR-07100RL"))
      (libsource (lib "eagle-import") (part "SMD-RES-100R-5%-1/8W(0805)"))
    )
    (comp (ref "R24")
      (value "15R")
      (footprint "eagle-import:R0603")
      (fields (field (name "MPN") "RC0603JR-0715RL"))
      (libsource (lib "eagle-import") (part "SMD-RES-15R-5%-1/10W(0603)"))
    )
  )
  (nets
    (net (code "1") (name "+12V") (class "Default")
      (node (ref "Q1") (pin "3") (pinfunction "D_3") (pintype "passive"))
      (node (ref "Q2") (pin "3") (pinfunction "D_3") (pintype "passive"))
      (node (ref "Q3") (pin "3") (pinfunction "D_3") (pintype "passive"))
      (node (ref "Q4") (pin "3") (pinfunction "D_3") (pintype "passive"))
      (node (ref "Q5") (pin "3") (pinfunction "D_3") (pintype "passive"))
      (node (ref "Q6") (pin "3") (pinfunction "D_3") (pintype "passive"))
      (node (ref "Q7") (pin "3") (pinfunction "D_3") (pintype "passive"))
      (node (ref "Q8") (pin "3") (pinfunction "D_3") (pintype "passive"))
    )
    (net (code "2") (name "D1") (class "Default")
      (node (ref "CON1") (pin "1") (pinfunction "1_1") (pintype "passive"))
      (node (ref "R3") (pin "1") (pinfunction "1_1") (pintype "passive"))
    )
    (net (code "3") (name "D2") (class "Default")
      (node (ref "CON1") (pin "2") (pinfunction "2_2") (pintype "passive"))
      (node (ref "R6") (pin "1") (pinfunction "1_1") (pintype "passive"))
    )
    (net (code "4") (name "D3") (class "Default")
      (node (ref "CON1") (pin "3") (pinfunction "3_3") (pintype "passive"))
      (node (ref "R9") (pin "1") (pinfunction "1_1") (pintype "passive"))
    )
    (net (code "5") (name "D4") (class "Default")
      (node (ref "CON1") (pin "4") (pinfunction "4_4") (pintype "passive"))
      (node (ref "R12") (pin "1") (pinfunction "1_1") (pintype "passive"))
    )
    (net (code "6") (name "D5") (class "Default")
      (node (ref "CON1") (pin "5") (pinfunction "5_5") (pintype "passive"))
      (node (ref "R15") (pin "1") (pinfunction "1_1") (pintype "passive"))
    )
    (net (code "7") (name "D6") (class "Default")
      (node (ref "CON1") (pin "6") (pinfunction "6_6") (pintype "passive"))
      (node (ref "R18") (pin "1") (pinfunction "1_1") (pintype "passive"))
    )
    (net (code "8") (name "D7") (class "Default")
      (node (ref "CON1") (pin "7") (pinfunction "7_7") (pintype "passive"))
      (node (ref "R21") (pin "1") (pinfunction "1_1") (pintype "passive"))
    )
    (net (code "9") (name "D8") (class "Default")
      (node (ref "CON1") (pin "8") (pinfunction "8_8") (pintype "passive"))
      (node (ref "R24") (pin "1") (pinfunction "1_1") (pintype "passive"))
    )
    (net (code "10") (name "GND") (class "Default")
      (node (ref "R1") (pin "1") (pinfunction "1_1") (pintype "passive"))
      (node (ref "R10") (pin "1") (pinfunction "1_1") (pintype "passive"))
      (node (ref "R11") (pin "1") (pinfunction "1_1") (pintype "passive"))
      (node (ref "R13") (pin "1") (pinfunction "1_1") (pintype "passive"))
      (node (ref "R14") (pin "1") (pinfunction "1_1") (pintype "passive"))
      (node (ref "R16") (pin "1") (pinfunction "1_1") (pintype "passive"))
      (node (ref "R17") (pin "1") (pinfunction "1_1") (pintype "passive"))
      (node (ref "R19") (pin "1") (pinfunction "1_1") (pintype "passive"))
      (node (ref "R2") (pin "1") (pinfunction "1_1") (pintype "passive"))
      (node (ref "R20") (pin "1") (pinfunction "1_1") (pintype "passive"))
      (node (ref "R22") (pin "1") (pinfunction "1_1") (pintype "passive"))
      (node (ref "R23") (pin "1") (pinfunction "1_1") (pintype "passive"))
      (node (ref "R4") (pin "1") (pinfunction "1_1") (pintype "passive"))
      (node (ref "R5") (pin "1") (pinfunction "1_1") (pintype "passive"))
      (node (ref "R7") (pin "1") (pinfunction "1_1") (pintype "passive"))
      (node (ref "R8") (pin "1") (pinfunction "1_1") (pintype "passive"))
    )
    (net (code "11") (name "Net-(D1-Pad-)") (class "Default")
      (node (ref "D1") (pin "-") (pinfunction "-_-") (pintype "passive"))
      (node (ref "D2") (pin "+") (pinfunction "+_+") (pintype "passive"))
    )
    (net (code "12") (name "Net-(D2-Pad-)") (class "Default")
      (node (ref "D2") (pin "-") (pinfunction "-_-") (pintype "passive"))
      (node (ref "D3") (pin "+") (pinfunction "+_+") (pintype "passive"))
    )
    (net (code "13") (name "Net-(D3-Pad-)") (class "Default")
      (node (ref "D3") (pin "-") (pinfunction "-_-") (pintype "passive"))
      (node (ref "D4") (pin "+") (pinfunction "+_+") (pintype "passive"))
    )
    (net (code "14") (name "Net-(D4-Pad-)") (class "Default")
      (node (ref "D4") (pin "-") (pinfunction "-_-") (pintype "passive"))
      (node (ref "D5") (pin "+") (pinfunction "+_+") (pintype "passive"))
    )
    (net (code "15") (name "Net-(D5-Pad-)") (class "Default")
      (node (ref "D5") (pin "-") (pinfunction "-_-") (pintype "passive"))
      (node (ref "R1") (pin "2") (pinfunction "2_2") (pintype "passive"))
    )
    (net (code "16") (name "Net-(D6-Pad-)") (class "Default")
      (node (ref "D6") (pin "-") (pinfunction "-_-") (pintype "passive"))
      (node (ref "D7") (pin "+") (pinfunction "+_+") (pintype "passive"))
    )
    (net (code "17") (name "Net-(D7-Pad-)") (class "Default")
      (node (ref "D7") (pin "-") (pinfunction "-_-") (pintype "passive"))
      (node (ref "D8") (pin "+") (pinfunction "+_+") (pintype "passive"))
    )
    (net (code "18") (name "Net-(D8-Pad-)") (class "Default")
      (node (ref "D8") (pin "-") (pinfunction "-_-") (pintype "passive"))
      (node (ref "D9") (pin "+") (pinfunction "+_+") (pintype "passive"))
    )
    (net (code "19") (name "Net-(D10-Pad+)") (class "Default")
      (node (ref "D10") (pin "+") (pinfunction "+_+") (pintype "passive"))
      (node (ref "D9") (pin "-") (pinfunction "-_-") (pintype "passive"))
    )
    (net (code "20") (name "Net-(D10-Pad-)") (class "Default")
      (node (ref "D10") (pin "-") (pinfunction "-_-") (pintype "passive"))
      (node (ref "R2") (pin "2") (pinfunction "2_2") (pintype "passive"))
    )
    (net (code "21") (name "Net-(D11-Pad-)") (class "Default")
      (node (ref "D11") (pin "-") (pinfunction "-_-") (pintype "passive"))
      (node (ref "D12") (pin "+") (pinfunction "+_+") (pintype "passive"))
    )
    (net (code "22") (name "Net-(D12-Pad-)") (class "Default")
      (node (ref "D12") (pin "-") (pinfunction "-_-") (pintype "passive"))
      (node (ref "D13") (pin "+") (pinfunction "+_+") (pintype "passive"))
    )
    (net (code "23") (name "Net-(D13-Pad-)") (class "Default")
      (node (ref "D13") (pin "-") (pinfunction "-_-") (pintype "passive"))
      (node (ref "D14") (pin "+") (pinfunction "+_+") (pintype "passive"))
    )
    (net (code "24") (name "Net-(D14-Pad-)") (class "Default")
      (node (ref "D14") (pin "-") (pinfunction "-_-") (pintype "passive"))
      (node (ref "D15") (pin "+") (pinfunction "+_+") (pintype "passive"))
    )
    (net (code "25") (name "Net-(D15-Pad-)") (class "Default")
      (node (ref "D15") (pin "-") (pinfunction "-_-") (pintype "passive"))
      (node (ref "R4") (pin "2") (pinfunction "2_2") (pintype "passive"))
    )
    (net (code "26") (name "Net-(D16-Pad-)") (class "Default")
      (node (ref "D16") (pin "-") (pinfunction "-_-") (pintype "passive"))
      (node (ref "D17") (pin "+") (pinfunction "+_+") (pintype "passive"))
    )
    (net (code "27") (name "Net-(D17-Pad-)") (class "Default")
      (node (ref "D17") (pin "-") (pinfunction "-_-") (pintype "passive"))
      (node (ref "D18") (pin "+") (pinfunction "+_+") (pintype "passive"))
    )
    (net (code "28") (name "Net-(D18-Pad-)") (class "Default")
      (node (ref "D18") (pin "-") (pinfunction "-_-") (pintype "passive"))
      (node (ref "D19") (pin "+") (pinfunction "+_+") (pintype "passive"))
    )
    (net (code "29") (name "Net-(D19-Pad-)") (class "Default")
      (node (ref "D19") (pin "-") (pinfunction "-_-") (pintype "passive"))
      (node (ref "D20") (pin "+") (pinfunction "+_+") (pintype "passive"))
    )
    (net (code "30") (name "Net-(D20-Pad-)") (class "Default")
      (node (ref "D20") (pin "-") (pinfunction "-_-") (pintype "passive"))
      (node (ref "R5") (pin "2") (pinfunction "2_2") (pintype "passive"))
    )
    (net (code "31") (name "Net-(D21-Pad-)") (class "Default")
      (node (ref "D21") (pin "-") (pinfunction "-_-") (pintype "passive"))
      (node (ref "D22") (pin "+") (pinfunction "+_+") (pintype "passive"))
    )
    (net (code "32") (name "Net-(D22-Pad-)") (class "Default")
      (node (ref "D22") (pin "-") (pinfunction "-_-") (pintype "passive"))
      (node (ref "D23") (pin "+") (pinfunction "+_+") (pintype "passive"))
    )
    (net (code "33") (name "Net-(D23-Pad-)") (class "Default")
      (node (ref "D23") (pin "-") (pinfunction "-_-") (pintype "passive"))
      (node (ref "D24") (pin "+") (pinfunction "+_+") (pintype "passive"))
    )
    (net (code "34") (name "Net-(D24-Pad-)") (class "Default")
      (node (ref "D24") (pin "-") (pinfunction "-_-") (pintype "passive"))
      (node (ref "D25") (pin "+") (pinfunction "+_+") (pintype "passive"))
    )
    (net (code "35") (name "Net-(D25-Pad-)") (class "Default")
      (node (ref "D25") (pin "-") (pinfunction "-_-") (pintype "passive"))
      (node (ref "R7") (pin "2") (pinfunction "2_2") (pintype "passive"))
    )
    (net (code "36") (name "Net-(D26-Pad-)") (class "Default")
      (node (ref "D26") (pin "-") (pinfunction "-_-") (pintype "passive"))
      (node (ref "D27") (pin "+") (pinfunction "+_+") (pintype "passive"))
    )
    (net (code "37") (name "Net-(D27-Pad-)") (class "Default")
      (node (ref "D27") (pin "-") (pinfunction "-_-") (pintype "passive"))
      (node (ref "D28") (pin "+") (pinfunction "+_+") (pintype "passive"))
    )
    (net (code "38") (name "Net-(D28-Pad-)") (class "Default")
      (node (ref "D28") (pin "-") (pinfunction "-_-") (pintype "passive"))
      (node (ref "D29") (pin "+") (pinfunction "+_+") (pintype "passive"))
    )
    (net (code "39") (name "Net-(D29-Pad-)") (class "Default")
      (node (ref "D29") (pin "-") (pinfunction "-_-") (pintype "passive"))
      (node (ref "D30") (pin "+") (pinfunction "+_+") (pintype "passive"))
    )
    (net (code "40") (name "Net-(D30-Pad-)") (class "Default")
      (node (ref "D30") (pin "-") (pinfunction "-_-") (pintype "passive"))
      (node (ref "R8") (pin "2") (pinfunction "2_2") (pintype "passive"))
    )
    (net (code "41") (name "Net-(D31-Pad-)") (class "Default")
      (node (ref "D31") (pin "-") (pinfunction "-_-") (pintype "passive"))
      (node (ref "D32") (pin "+") (pinfunction "+_+") (pintype "passive"))
    )
    (net (code "42") (name "Net-(D32-Pad-)") (class "Default")
      (node (ref "D32") (pin "-") (pinfunction "-_-") (pintype "passive"))
      (node (ref "D33") (pin "+") (pinfunction "+_+") (pintype "passive"))
    )
    (net (code "43") (name "Net-(D33-Pad-)") (class "Default")
      (node (ref "D33") (pin "-") (pinfunction "-_-") (pintype "passive"))
      (node (ref "D34") (pin "+") (pinfunction "+_+") (pintype "passive"))
    )
    (net (code "44") (name "Net-(D34-Pad-)") (class "Default")
      (node (ref "D34") (pin "-") (pinfunction "-_-") (pintype "passive"))
      (node (ref "D35") (pin "+") (pinfunction "+_+") (pintype "passive"))
    )
    (net (code "45") (name "Net-(D35-Pad-)") (class "Default")
      (node (ref "D35") (pin "-") (pinfunction "-_-") (pintype "passive"))
      (node (ref "R10") (pin "2") (pinfunction "2_2") (pintype "passive"))
    )
    (net (code "46") (name "Net-(D36-Pad-)") (class "Default")
      (node (ref "D36") (pin "-") (pinfunction "-_-") (pintype "passive"))
      (node (ref "D37") (pin "+") (pinfunction "+_+") (pintype "passive"))
    )
    (net (code "47") (name "Net-(D37-Pad-)") (class "Default")
      (node (ref "D37") (pin "-") (pinfunction "-_-") (pintype "passive"))
      (node (ref "D38") (pin "+") (pinfunction "+_+") (pintype "passive"))
    )
    (net (code "48") (name "Net-(D38-Pad-)") (class "Default")
      (node (ref "D38") (pin "-") (pinfunction "-_-") (pintype "passive"))
      (node (ref "D39") (pin "+") (pinfunction "+_+") (pintype "passive"))
    )
    (net (code "49") (name "Net-(D39-Pad-)") (class "Default")
      (node (ref "D39") (pin "-") (pinfunction "-_-") (pintype "passive"))
      (node (ref "D40") (pin "+") (pinfunction "+_+") (pintype "passive"))
    )
    (net (code "50") (name "Net-(D40-Pad-)") (class "Default")
      (node (ref "D40") (pin "-") (pinfunction "-_-") (pintype "passive"))
      (node (ref "R11") (pin "2") (pinfunction "2_2") (pintype "passive"))
    )
    (net (code "51") (name "Net-(D41-Pad-)") (class "Default")
      (node (ref "D41") (pin "-") (pinfunction "-_-") (pintype "passive"))
      (node (ref "D42") (pin "+") (pinfunction "+_+") (pintype "passive"))
    )
    (net (code "52") (name "Net-(D42-Pad-)") (class "Default")
      (node (ref "D42") (pin "-") (pinfunction "-_-") (pintype "passive"))
      (node (ref "D43") (pin "+") (pinfunction "+_+") (pintype "passive"))
    )
    (net (code "53") (name "Net-(D43-Pad-)") (class "Default")
      (node (ref "D43") (pin "-") (pinfunction "-_-") (pintype "passive"))
      (node (ref "D44") (pin "+") (pinfunction "+_+") (pintype "passive"))
    )
    (net (code "54") (name "Net-(D44-Pad-)") (class "Default")
      (node (ref "D44") (pin "-") (pinfunction "-_-") (pintype "passive"))
      (node (ref "D45") (pin "+") (pinfunction "+_+") (pintype "passive"))
    )
    (net (code "55") (name "Net-(D45-Pad-)") (class "Default")
      (node (ref "D45") (pin "-") (pinfunction "-_-") (pintype "passive"))
      (node (ref "R13") (pin "2") (pinfunction "2_2") (pintype "passive"))
    )
    (net (code "56") (name "Net-(D46-Pad-)") (class "Default")
      (node (ref "D46") (pin "-") (pinfunction "-_-") (pintype "passive"))
      (node (ref "D47") (pin "+") (pinfunction "+_+") (pintype "passive"))
    )
    (net (code "57") (name "Net-(D47-Pad-)") (class "Default")
      (node (ref "D47") (pin "-") (pinfunction "-_-") (pintype "passive"))
      (node (ref "D48") (pin "+") (pinfunction "+_+") (pintype "passive"))
    )
    (net (code "58") (name "Net-(D48-Pad-)") (class "Default")
      (node (ref "D48") (pin "-") (pinfunction "-_-") (pintype "passive"))
      (node (ref "D49") (pin "+") (pinfunction "+_+") (pintype "passive"))
    )
    (net (code "59") (name "Net-(D49-Pad-)") (class "Default")
      (node (ref "D49") (pin "-") (pinfunction "-_-") (pintype "passive"))
      (node (ref "D50") (pin "+") (pinfunction "+_+") (pintype "passive"))
    )
    (net (code "60") (name "Net-(D50-Pad-)") (class "Default")
      (node (ref "D50") (pin "-") (pinfunction "-_-") (pintype "passive"))
      (node (ref "R14") (pin "2") (pinfunction "2_2") (pintype "passive"))
    )
    (net (code "61") (name "Net-(D51-Pad-)") (class "Default")
      (node (ref "D51") (pin "-") (pinfunction "-_-") (pintype "passive"))
      (node (ref "D52") (pin "+") (pinfunction "+_+") (pintype "passive"))
    )
    (net (code "62") (name "Net-(D52-Pad-)") (class "Default")
      (node (ref "D52") (pin "-") (pinfunction "-_-") (pintype "passive"))
      (node (ref "D53") (pin "+") (pinfunction "+_+") (pintype "passive"))
    )
    (net (code "63") (name "Net-(D53-Pad-)") (class "Default")
      (node (ref "D53") (pin "-") (pinfunction "-_-") (pintype "passive"))
      (node (ref "D54") (pin "+") (pinfunction "+_+") (pintype "passive"))
    )
    (net (code "64") (name "Net-(D54-Pad-)") (class "Default")
      (node (ref "D54") (pin "-") (pinfunction "-_-") (pintype "passive"))
      (node (ref "D55") (pin "+") (pinfunction "+_+") (pintype "passive"))
    )
    (net (code "65") (name "Net-(D55-Pad-)") (class "Default")
      (node (ref "D55") (pin "-") (pinfunction "-_-") (pintype "passive"))
      (node (ref "R16") (pin "2") (pinfunction "2_2") (pintype "passive"))
    )
    (net (code "66") (name "Net-(D56-Pad-)") (class "Default")
      (node (ref "D56") (pin "-") (pinfunction "-_-") (pintype "passive"))
      (node (ref "D57") (pin "+") (pinfunction "+_+") (pintype "passive"))
    )
    (net (code "67") (name "Net-(D57-Pad-)") (class "Default")
      (node (ref "D57") (pin "-") (pinfunction "-_-") (pintype "passive"))
      (node (ref "D58") (pin "+") (pinfunction "+_+") (pintype "passive"))
    )
    (net (code "68") (name "Net-(D58-Pad-)") (class "Default")
      (node (ref "D58") (pin "-") (pinfunction "-_-") (pintype "passive"))
      (node (ref "D59") (pin "+") (pinfunction "+_+") (pintype "passive"))
    )
    (net (code "69") (name "Net-(D59-Pad-)") (class "Default")
      (node (ref "D59") (pin "-") (pinfunction "-_-") (pintype "passive"))
      (node (ref "D60") (pin "+") (pinfunction "+_+") (pintype "passive"))
    )
    (net (code "70") (name "Net-(D60-Pad-)") (class "Default")
      (node (ref "D60") (pin "-") (pinfunction "-_-") (pintype "passive"))
      (node (ref "R17") (pin "2") (pinfunction "2_2") (pintype "passive"))
    )
    (net (code "71") (name "Net-(D61-Pad-)") (class "Default")
      (node (ref "D61") (pin "-") (pinfunction "-_-") (pintype "passive"))
      (node (ref "D62") (pin "+") (pinfunction "+_+") (pintype "passive"))
    )
    (net (code "72") (name "Net-(D62-Pad-)") (class "Default")
      (node (ref "D62") (pin "-") (pinfunction "-_-") (pintype "passive"))
      (node (ref "D63") (pin "+") (pinfunction "+_+") (pintype "passive"))
    )
    (net (code "73") (name "Net-(D63-Pad-)") (class "Default")
      (node (ref "D63") (pin "-") (pinfunction "-_-") (pintype "passive"))
      (node (ref "D64") (pin "+") (pinfunction "+_+") (pintype "passive"))
    )
    (net (code "74") (name "Net-(D64-Pad-)") (class "Default")
      (node (ref "D64") (pin "-") (pinfunction "-_-") (pintype "passive"))
      (node (ref "D65") (pin "+") (pinfunction "+_+") (pintype "passive"))
    )
    (net (code "75") (name "Net-(D65-Pad-)") (class "Default")
      (node (ref "D65") (pin "-") (pinfunction "-_-") (pintype "passive"))
      (node (ref "R19") (pin "2") (pinfunction "2_2") (pintype "passive"))
    )
    (net (code "76") (name "Net-(D66-Pad-)") (class "Default")
      (node (ref "D66") (pin "-") (pinfunction "-_-") (pintype "passive"))
      (node (ref "D67") (pin "+") (pinfunction "+_+") (pintype "passive"))
    )
    (net (code "77") (name "Net-(D67-Pad-)") (class "Default")
      (node (ref "D67") (pin "-") (pinfunction "-_-") (pintype "passive"))
      (node (ref "D68") (pin "+") (pinfunction "+_+") (pintype "passive"))
    )
    (net (code "78") (name "Net-(D68-Pad-)") (class "Default")
      (node (ref "D68") (pin "-") (pinfunction "-_-") (pintype "passive"))
      (node (ref "D69") (pin "+") (pinfunction "+_+") (pintype "passive"))
    )
    (net (code "79") (name "Net-(D69-Pad-)") (class "Default")
      (node (ref "D69") (pin "-") (pinfunction "-_-") (pintype "passive"))
      (node (ref "D70") (pin "+") (pinfunction "+_+") (pintype "passive"))
    )
    (net (code "80") (name "Net-(D70-Pad-)") (class "Default")
      (node (ref "D70") (pin "-") (pinfunction "-_-") (pintype "passive"))
      (node (ref "R20") (pin "2") (pinfunction "2_2") (pintype "passive"))
    )
    (net (code "81") (name "Net-(D71-Pad-)") (class "Default")
      (node (ref "D71") (pin "-") (pinfunction "-_-") (pintype "passive"))
      (node (ref "D72") (pin "+") (pinfunction "+_+") (pintype "passive"))
    )
    (net (code "82") (name "Net-(D72-Pad-)") (class "Default")
      (node (ref "D72") (pin "-") (pinfunction "-_-") (pintype "passive"))
      (node (ref "D73") (pin "+") (pinfunction "+_+") (pintype "passive"))
    )
    (net (code "83") (name "Net-(D73-Pad-)") (class "Default")
      (node (ref "D73") (pin "-") (pinfunction "-_-") (pintype "passive"))
      (node (ref "D74") (pin "+") (pinfunction "+_+") (pintype "passive"))
    )
    (net (code "84") (name "Net-(D74-Pad-)") (class "Default")
      (node (ref "D74") (pin "-") (pinfunction "-_-") (pintype "passive"))
      (node (ref "D75") (pin "+") (pinfunction "+_+") (pintype "passive"))
    )
    (net (code "85") (name "Net-(D75-Pad-)") (class "Default")
      (node (ref "D75") (pin "-") (pinfunction "-_-") (pintype "passive"))
      (node (ref "R22") (pin "2") (pinfunction "2_2") (pintype "passive"))
    )
    (net (code "86") (name "Net-(D76-Pad-)") (class "Default")
      (node (ref "D76") (pin "-") (pinfunction "-_-") (pintype "passive"))
      (node (ref "D77") (pin "+") (pinfunction "+_+") (pintype "passive"))
    )
    (net (code "87") (name "Net-(D77-Pad-)") (class "Default")
      (node (ref "D77") (pin "-") (pinfunction "-_-") (pintype "passive"))
      (node (ref "D78") (pin "+") (pinfunction "+_+") (pintype "passive"))
    )
    (net (code "88") (name "Net-(D78-Pad-)") (class "Default")
      (node (ref "D78") (pin "-") (pinfunction "-_-") (pintype "passive"))
      (node (ref "D79") (pin "+") (pinfunction "+_+") (pintype "passive"))
    )
    (net (code "89") (name "Net-(D79-Pad-)") (class "Default")
      (node (ref "D79") (pin "-") (pinfunction "-_-") (pintype "passive"))
      (node (ref "D80") (pin "+") (pinfunction "+_+") (pintype "passive"))
    )
    (net (code "90") (name "Net-(D80-Pad-)") (class "Default")
      (node (ref "D80") (pin "-") (pinfunction "-_-") (pintype "passive"))
      (node (ref "R23") (pin "2") (pinfunction "2_2") (pintype "passive"))
    )
    (net (code "91") (name "Net-(Q1-G)") (class "Default")
      (node (ref "Q1") (pin "1") (pinfunction "G_1") (pintype "passive"))
      (node (ref "R3") (pin "2") (pinfunction "2_2") (pintype "passive"))
    )
    (net (code "92") (name "Net-(Q1-S)") (class "Default")
      (node (ref "D1") (pin "+") (pinfunction "+_+") (pintype "passive"))
      (node (ref "D6") (pin "+") (pinfunction "+_+") (pintype "passive"))
      (node (ref "Q1") (pin "2") (pinfunction "S_2") (pintype "passive"))
    )
    (net (code "93") (name "Net-(Q2-G)") (class "Default")
      (node (ref "Q2") (pin "1") (pinfunction "G_1") (pintype "passive"))
      (node (ref "R6") (pin "2") (pinfunction "2_2") (pintype "passive"))
    )
    (net (code "94") (name "Net-(Q2-S)") (class "Default")
      (node (ref "D11") (pin "+") (pinfunction "+_+") (pintype "passive"))
      (node (ref "D16") (pin "+") (pinfunction "+_+") (pintype "passive"))
      (node (ref "Q2") (pin "2") (pinfunction "S_2") (pintype "passive"))
    )
    (net (code "95") (name "Net-(Q3-G)") (class "Default")
      (node (ref "Q3") (pin "1") (pinfunction "G_1") (pintype "passive"))
      (node (ref "R9") (pin "2") (pinfunction "2_2") (pintype "passive"))
    )
    (net (code "96") (name "Net-(Q3-S)") (class "Default")
      (node (ref "D21") (pin "+") (pinfunction "+_+") (pintype "passive"))
      (node (ref "D26") (pin "+") (pinfunction "+_+") (pintype "passive"))
      (node (ref "Q3") (pin "2") (pinfunction "S_2") (pintype "passive"))
    )
    (net (code "97") (name "Net-(Q4-G)") (class "Default")
      (node (ref "Q4") (pin "1") (pinfunction "G_1") (pintype "passive"))
      (node (ref "R12") (pin "2") (pinfunction "2_2") (pintype "passive"))
    )
    (net (code "98") (name "Net-(Q4-S)") (class "Default")
      (node (ref "D31") (pin "+") (pinfunction "+_+") (pintype "passive"))
      (node (ref "D36") (pin "+") (pinfunction "+_+") (pintype "passive"))
      (node (ref "Q4") (pin "2") (pinfunction "S_2") (pintype "passive"))
    )
    (net (code "99") (name "Net-(Q5-G)") (class "Default")
      (node (ref "Q5") (pin "1") (pinfunction "G_1") (pintype "passive"))
      (node (ref "R15") (pin "2") (pinfunction "2_2") (pintype "passive"))
    )
    (net (code "100") (name "Net-(Q5-S)") (class "Default")
      (node (ref "D41") (pin "+") (pinfunction "+_+") (pintype "passive"))
      (node (ref "D46") (pin "+") (pinfunction "+_+") (pintype "passive"))
      (node (ref "Q5") (pin "2") (pinfunction "S_2") (pintype "passive"))
    )
    (net (code "101") (name "Net-(Q6-G)") (class "Default")
      (node (ref "Q6") (pin "1") (pinfunction "G_1") (pintype "passive"))
      (node (ref "R18") (pin "2") (pinfunction "2_2") (pintype "passive"))
    )
    (net (code "102") (name "Net-(Q6-S)") (class "Default")
      (node (ref "D51") (pin "+") (pinfunction "+_+") (pintype "passive"))
      (node (ref "D56") (pin "+") (pinfunction "+_+") (pintype "passive"))
      (node (ref "Q6") (pin "2") (pinfunction "S_2") (pintype "passive"))
    )
    (net (code "103") (name "Net-(Q7-G)") (class "Default")
      (node (ref "Q7") (pin "1") (pinfunction "G_1") (pintype "passive"))
      (node (ref "R21") (pin "2") (pinfunction "2_2") (pintype "passive"))
    )
    (net (code "104") (name "Net-(Q7-S)") (class "Default")
      (node (ref "D61") (pin "+") (pinfunction "+_+") (pintype "passive"))
      (node (ref "D66") (pin "+") (pinfunction "+_+") (pintype "passive"))
      (node (ref "Q7") (pin "2") (pinfunction "S_2") (pintype "passive"))
    )
    (net (code "105") (name "Net-(Q8-G)") (class "Default")
      (node (ref "Q8") (pin "1") (pinfunction "G_1") (pintype "passive"))
      (node (ref "R24") (pin "2") (pinfunction "2_2") (pintype "passive"))
    )
    (net (code "106") (name "Net-(Q8-S)") (class "Default")
      (node (ref "D71") (pin "+") (pinfunction "+_+") (pintype "passive"))
      (node (ref "D76") (pin "+") (pinfunction "+_+") (pintype "passive"))
      (node (ref "Q8") (pin "2") (pinfunction "S_2") (pintype "passive"))
    )
    (net (code "107") (name "unconnected-(CON1-Pad9)") (class "Default")
      (node (ref "CON1") (pin "9") (pinfunction "9_9") (pintype "passive"))
    )
    (net (code "108") (name "unconnected-(CON1-Pad10)") (class "Default")
      (node (ref "CON1") (pin "10") (pinfunction "10_10") (pintype "passive"))
    )
    (net (code "109") (name "unconnected-(CON1-Pad11)") (class "Default")
      (node (ref "CON1") (pin "11") (pinfunction "11_11") (pintype "passive"))
    )
    (net (code "110") (name "unconnected-(CON1-Pad12)") (class "Default")
      (node (ref "CON1") (pin "12") (pinfunction "12_12") (pintype "passive"))
    )
    (net (code "111") (name "unconnected-(CON1-Pad13)") (class "Default")
      (node (ref "CON1") (pin "13") (pinfunction "13_13") (pintype "passive"))
    )
    (net (code "112") (name "unconnected-(CON1-Pad14)") (class "Default")
      (node (ref "CON1") (pin "14") (pinfunction "14_14") (pintype "passive"))
    )
    (net (code "113") (name "unconnected-(CON1-Pad15)") (class "Default")
      (node (ref "CON1") (pin "15") (pinfunction "15_15") (pintype "passive"))
    )
    (net (code "114") (name "unconnected-(CON1-Pad16)") (class "Default")
      (node (ref "CON1") (pin "16") (pinfunction "16_16") (pintype "passive"))
    )
    (net (code "115") (name "unconnected-(CON1-Pad17)") (class "Default")
      (node (ref "CON1") (pin "17") (pinfunction "17_17") (pintype "passive"))
    )
    (net (code "116") (name "unconnected-(CON1-Pad18)") (class "Default")
      (node (ref "CON1") (pin "18") (pinfunction "18_18") (pintype "passive"))
    )
    (net (code "117") (name "unconnected-(CON1-Pad19)") (class "Default")
      (node (ref "CON1") (pin "19") (pinfunction "19_19") (pintype "passive"))
    )
    (net (code "118") (name "unconnected-(CON1-Pad20)") (class "Default")
      (node (ref "CON1") (pin "20") (pinfunction "20_20") (pintype "passive"))
    )
    (net (code "119") (name "unconnected-(CON1-Pad21)") (class "Default")
      (node (ref "CON1") (pin "21") (pinfunction "21_21") (pintype "passive"))
    )
    (net (code "120") (name "unconnected-(CON1-Pad22)") (class "Default")
      (node (ref "CON1") (pin "22") (pinfunction "22_22") (pintype "passive"))
    )
    (net (code "121") (name "unconnected-(CON1-Pad23)") (class "Default")
      (node (ref "CON1") (pin "23") (pinfunction "23_23") (pintype "passive"))
    )
    (net (code "122") (name "unconnected-(CON1-Pad24)") (class "Default")
      (node (ref "CON1") (pin "24") (pinfunction "24_24") (pintype "passive"))
    )
    (net (code "123") (name "unconnected-(CON1-Pad25)") (class "Default")
      (node (ref "CON1") (pin "25") (pinfunction "25_25") (pintype "passive"))
    )
    (net (code "124") (name "unconnected-(CON1-Pad26)") (class "Default")
      (node (ref "CON1") (pin "26") (pinfunction "26_26") (pintype "passive"))
    )
    (net (code "125") (name "unconnected-(CON1-Pad27)") (class "Default")
      (node (ref "CON1") (pin "27") (pinfunction "27_27") (pintype "passive"))
    )
    (net (code "126") (name "unconnected-(CON1-Pad28)") (class "Default")
      (node (ref "CON1") (pin "28") (pinfunction "28_28") (pintype "passive"))
    )
    (net (code "127") (name "unconnected-(CON1-Pad29)") (class "Default")
      (node (ref "CON1") (pin "29") (pinfunction "29_29") (pintype "passive"))
    )
    (net (code "128") (name "unconnected-(CON1-Pad30)") (class "Default")
      (node (ref "CON1") (pin "30") (pinfunction "30_30") (pintype "passive"))
    )
    (net (code "129") (name "unconnected-(CON1-Pad31)") (class "Default")
      (node (ref "CON1") (pin "31") (pinfunction "31_31") (pintype "passive"))
    )
    (net (code "130") (name "unconnected-(CON1-Pad32)") (class "Default")
      (node (ref "CON1") (pin "32") (pinfunction "32_32") (pintype "passive"))
    )
    (net (code "131") (name "unconnected-(CON1-Pad33)") (class "Default")
      (node (ref "CON1") (pin "33") (pinfunction "33_33") (pintype "passive"))
    )
    (net (code "132") (name "unconnected-(CON1-Pad34)") (class "Default")
      (node (ref "CON1") (pin "34") (pinfunction "34_34") (pintype "passive"))
    )
  )
)
